# croky_b_1_7_mini.net
KiCad netlist of a schematic drawn in EAGLE
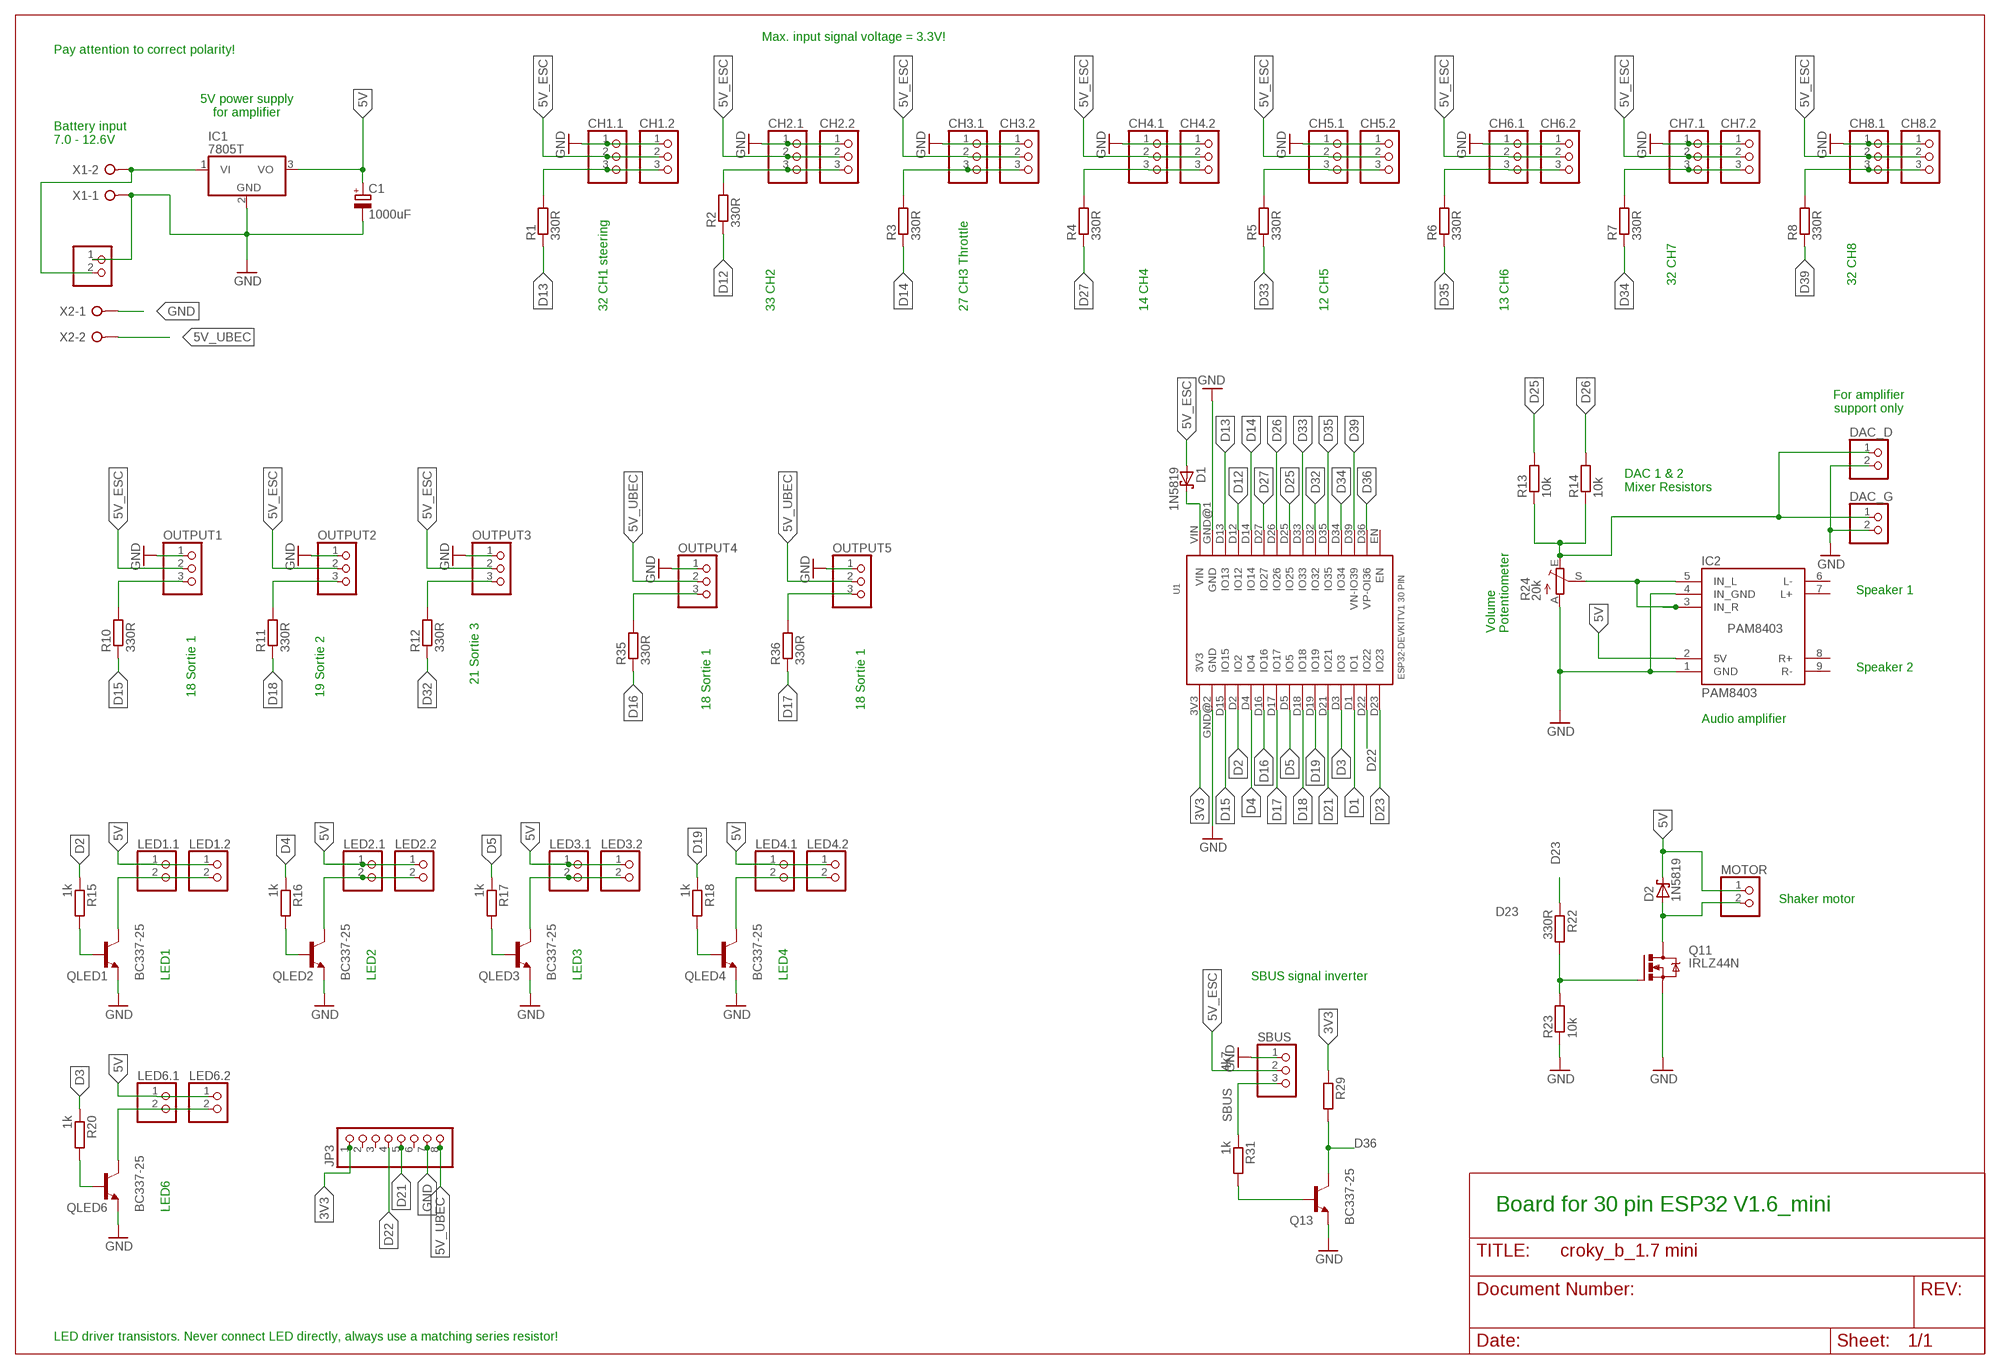
[diagram p0: schematic, sheet 1]

(export (version "E")
  (design (tool "Eeschema 10.0.6"))
  (components
    (comp (ref "C1")
      (value "1000uF")
      (footprint "eagle-import:E5-10,5")
      (libsource (lib "eagle-import") (part "CPOL-EUE5-10.5"))
    )
    (comp (ref "CH1.1")
      (value "PINHD-1X3")
      (footprint "eagle-import:1X03")
      (libsource (lib "eagle-import") (part "PINHD-1X3"))
    )
    (comp (ref "CH1.2")
      (value "PINHD-1X3")
      (footprint "eagle-import:1X03")
      (libsource (lib "eagle-import") (part "PINHD-1X3"))
    )
    (comp (ref "CH2.1")
      (value "PINHD-1X3")
      (footprint "eagle-import:1X03")
      (libsource (lib "eagle-import") (part "PINHD-1X3"))
    )
    (comp (ref "CH2.2")
      (value "PINHD-1X3")
      (footprint "eagle-import:1X03")
      (libsource (lib "eagle-import") (part "PINHD-1X3"))
    )
    (comp (ref "CH3.1")
      (value "PINHD-1X3")
      (footprint "eagle-import:1X03")
      (libsource (lib "eagle-import") (part "PINHD-1X3"))
    )
    (comp (ref "CH3.2")
      (value "PINHD-1X3")
      (footprint "eagle-import:1X03")
      (libsource (lib "eagle-import") (part "PINHD-1X3"))
    )
    (comp (ref "CH4.1")
      (value "PINHD-1X3")
      (footprint "eagle-import:1X03")
      (libsource (lib "eagle-import") (part "PINHD-1X3"))
    )
    (comp (ref "CH4.2")
      (value "PINHD-1X3")
      (footprint "eagle-import:1X03")
      (libsource (lib "eagle-import") (part "PINHD-1X3"))
    )
    (comp (ref "CH5.1")
      (value "PINHD-1X3")
      (footprint "eagle-import:1X03")
      (libsource (lib "eagle-import") (part "PINHD-1X3"))
    )
    (comp (ref "CH5.2")
      (value "PINHD-1X3")
      (footprint "eagle-import:1X03")
      (libsource (lib "eagle-import") (part "PINHD-1X3"))
    )
    (comp (ref "CH6.1")
      (value "PINHD-1X3")
      (footprint "eagle-import:1X03")
      (libsource (lib "eagle-import") (part "PINHD-1X3"))
    )
    (comp (ref "CH6.2")
      (value "PINHD-1X3")
      (footprint "eagle-import:1X03")
      (libsource (lib "eagle-import") (part "PINHD-1X3"))
    )
    (comp (ref "CH7.1")
      (value "PINHD-1X3")
      (footprint "eagle-import:1X03")
      (libsource (lib "eagle-import") (part "PINHD-1X3"))
    )
    (comp (ref "CH7.2")
      (value "PINHD-1X3")
      (footprint "eagle-import:1X03")
      (libsource (lib "eagle-import") (part "PINHD-1X3"))
    )
    (comp (ref "CH8.1")
      (value "PINHD-1X3")
      (footprint "eagle-import:1X03")
      (libsource (lib "eagle-import") (part "PINHD-1X3"))
    )
    (comp (ref "CH8.2")
      (value "PINHD-1X3")
      (footprint "eagle-import:1X03")
      (libsource (lib "eagle-import") (part "PINHD-1X3"))
    )
    (comp (ref "D1")
      (value "1N5819")
      (footprint "eagle-import:DO35-7")
      (libsource (lib "eagle-import") (part "SCHOTTKY-DIODEDO35-7"))
    )
    (comp (ref "D2")
      (value "1N5819")
      (footprint "eagle-import:DO35-7")
      (libsource (lib "eagle-import") (part "SCHOTTKY-DIODEDO35-7"))
    )
    (comp (ref "DAC_D")
      (value "PINHD-1X2")
      (footprint "eagle-import:1X02")
      (libsource (lib "eagle-import") (part "PINHD-1X2"))
    )
    (comp (ref "DAC_G")
      (value "PINHD-1X2")
      (footprint "eagle-import:1X02")
      (libsource (lib "eagle-import") (part "PINHD-1X2"))
    )
    (comp (ref "IC1")
      (value "7805T")
      (footprint "eagle-import:TO220H")
      (libsource (lib "eagle-import") (part "78T05"))
    )
    (comp (ref "IC2")
      (value "PAM8403")
      (footprint "eagle-import:PAM8403")
      (libsource (lib "eagle-import") (part "PAM8403"))
    )
    (comp (ref "JP3")
      (value "PINHD-1X8")
      (footprint "eagle-import:1X08")
      (libsource (lib "eagle-import") (part "PINHD-1X8"))
    )
    (comp (ref "LED1.1")
      (value "PINHD-1X2")
      (footprint "eagle-import:1X02")
      (libsource (lib "eagle-import") (part "PINHD-1X2"))
    )
    (comp (ref "LED1.2")
      (value "PINHD-1X2")
      (footprint "eagle-import:1X02")
      (libsource (lib "eagle-import") (part "PINHD-1X2"))
    )
    (comp (ref "LED2.1")
      (value "PINHD-1X2")
      (footprint "eagle-import:1X02")
      (libsource (lib "eagle-import") (part "PINHD-1X2"))
    )
    (comp (ref "LED2.2")
      (value "PINHD-1X2")
      (footprint "eagle-import:1X02")
      (libsource (lib "eagle-import") (part "PINHD-1X2"))
    )
    (comp (ref "LED3.1")
      (value "PINHD-1X2")
      (footprint "eagle-import:1X02")
      (libsource (lib "eagle-import") (part "PINHD-1X2"))
    )
    (comp (ref "LED3.2")
      (value "PINHD-1X2")
      (footprint "eagle-import:1X02")
      (libsource (lib "eagle-import") (part "PINHD-1X2"))
    )
    (comp (ref "LED4.1")
      (value "PINHD-1X2")
      (footprint "eagle-import:1X02")
      (libsource (lib "eagle-import") (part "PINHD-1X2"))
    )
    (comp (ref "LED4.2")
      (value "PINHD-1X2")
      (footprint "eagle-import:1X02")
      (libsource (lib "eagle-import") (part "PINHD-1X2"))
    )
    (comp (ref "LED6.1")
      (value "PINHD-1X2")
      (footprint "eagle-import:1X02")
      (libsource (lib "eagle-import") (part "PINHD-1X2"))
    )
    (comp (ref "LED6.2")
      (value "PINHD-1X2")
      (footprint "eagle-import:1X02")
      (libsource (lib "eagle-import") (part "PINHD-1X2"))
    )
    (comp (ref "MOTOR")
      (value "PINHD-1X2")
      (footprint "eagle-import:1X02")
      (libsource (lib "eagle-import") (part "PINHD-1X2"))
    )
    (comp (ref "MOTOR2")
      (value "PINHD-1X2")
      (footprint "eagle-import:1X02")
      (libsource (lib "eagle-import") (part "PINHD-1X2"))
    )
    (comp (ref "OUTPUT1")
      (value "PINHD-1X3")
      (footprint "eagle-import:1X03")
      (libsource (lib "eagle-import") (part "PINHD-1X3"))
    )
    (comp (ref "OUTPUT2")
      (value "PINHD-1X3")
      (footprint "eagle-import:1X03")
      (libsource (lib "eagle-import") (part "PINHD-1X3"))
    )
    (comp (ref "OUTPUT3")
      (value "PINHD-1X3")
      (footprint "eagle-import:1X03")
      (libsource (lib "eagle-import") (part "PINHD-1X3"))
    )
    (comp (ref "OUTPUT4")
      (value "PINHD-1X3")
      (footprint "eagle-import:1X03")
      (libsource (lib "eagle-import") (part "PINHD-1X3"))
    )
    (comp (ref "OUTPUT5")
      (value "PINHD-1X3")
      (footprint "eagle-import:1X03")
      (libsource (lib "eagle-import") (part "PINHD-1X3"))
    )
    (comp (ref "Q11")
      (value "IRLZ44N")
      (footprint "eagle-import:TO220BV")
      (libsource (lib "eagle-import") (part "IRF540"))
    )
    (comp (ref "Q13")
      (value "BC337-25")
      (footprint "eagle-import:TO92")
      (libsource (lib "eagle-import") (part "BC337-25"))
    )
    (comp (ref "QLED1")
      (value "BC337-25")
      (footprint "eagle-import:TO92")
      (libsource (lib "eagle-import") (part "BC337-25"))
    )
    (comp (ref "QLED2")
      (value "BC337-25")
      (footprint "eagle-import:TO92")
      (libsource (lib "eagle-import") (part "BC337-25"))
    )
    (comp (ref "QLED3")
      (value "BC337-25")
      (footprint "eagle-import:TO92")
      (libsource (lib "eagle-import") (part "BC337-25"))
    )
    (comp (ref "QLED4")
      (value "BC337-25")
      (footprint "eagle-import:TO92")
      (libsource (lib "eagle-import") (part "BC337-25"))
    )
    (comp (ref "QLED6")
      (value "BC337-25")
      (footprint "eagle-import:TO92")
      (libsource (lib "eagle-import") (part "BC337-25"))
    )
    (comp (ref "R1")
      (value "330R")
      (footprint "eagle-import:0207_2V")
      (libsource (lib "eagle-import") (part "R-EU_0207/2V"))
    )
    (comp (ref "R2")
      (value "330R")
      (footprint "eagle-import:0207_2V")
      (libsource (lib "eagle-import") (part "R-EU_0207/2V"))
    )
    (comp (ref "R3")
      (value "330R")
      (footprint "eagle-import:0207_2V")
      (fields (field (name "SPICEPREFIX") "R"))
      (libsource (lib "eagle-import") (part "R-EU_0207/2V"))
    )
    (comp (ref "R4")
      (value "330R")
      (footprint "eagle-import:0207_2V")
      (libsource (lib "eagle-import") (part "R-EU_0207/2V"))
    )
    (comp (ref "R5")
      (value "330R")
      (footprint "eagle-import:0207_2V")
      (libsource (lib "eagle-import") (part "R-EU_0207/2V"))
    )
    (comp (ref "R6")
      (value "330R")
      (footprint "eagle-import:0207_2V")
      (libsource (lib "eagle-import") (part "R-EU_0207/2V"))
    )
    (comp (ref "R7")
      (value "330R")
      (footprint "eagle-import:0207_2V")
      (libsource (lib "eagle-import") (part "R-EU_0207/2V"))
    )
    (comp (ref "R8")
      (value "330R")
      (footprint "eagle-import:0207_2V")
      (libsource (lib "eagle-import") (part "R-EU_0207/2V"))
    )
    (comp (ref "R10")
      (value "330R")
      (footprint "eagle-import:0207_2V")
      (libsource (lib "eagle-import") (part "R-EU_0207/2V"))
    )
    (comp (ref "R11")
      (value "330R")
      (footprint "eagle-import:0207_2V")
      (libsource (lib "eagle-import") (part "R-EU_0207/2V"))
    )
    (comp (ref "R12")
      (value "330R")
      (footprint "eagle-import:0207_2V")
      (libsource (lib "eagle-import") (part "R-EU_0207/2V"))
    )
    (comp (ref "R13")
      (value "10k")
      (footprint "eagle-import:0207_10")
      (libsource (lib "eagle-import") (part "R-EU_0207/10"))
    )
    (comp (ref "R14")
      (value "10k")
      (footprint "eagle-import:0207_10")
      (libsource (lib "eagle-import") (part "R-EU_0207/10"))
    )
    (comp (ref "R15")
      (value "1k")
      (footprint "eagle-import:0207_2V")
      (libsource (lib "eagle-import") (part "R-EU_0207/2V"))
    )
    (comp (ref "R16")
      (value "1k")
      (footprint "eagle-import:0207_2V")
      (libsource (lib "eagle-import") (part "R-EU_0207/2V"))
    )
    (comp (ref "R17")
      (value "1k")
      (footprint "eagle-import:0207_2V")
      (libsource (lib "eagle-import") (part "R-EU_0207/2V"))
    )
    (comp (ref "R18")
      (value "1k")
      (footprint "eagle-import:0207_2V")
      (libsource (lib "eagle-import") (part "R-EU_0207/2V"))
    )
    (comp (ref "R20")
      (value "1k")
      (footprint "eagle-import:0207_2V")
      (libsource (lib "eagle-import") (part "R-EU_0207/2V"))
    )
    (comp (ref "R22")
      (value "330R")
      (footprint "eagle-import:0207_2V")
      (libsource (lib "eagle-import") (part "R-EU_0207/2V"))
    )
    (comp (ref "R23")
      (value "10k")
      (footprint "eagle-import:0207_2V")
      (libsource (lib "eagle-import") (part "R-EU_0207/2V"))
    )
    (comp (ref "R24")
      (value "20k")
      (footprint "eagle-import:S64W")
      (libsource (lib "eagle-import") (part "TRIM_EU-S64W"))
    )
    (comp (ref "R29")
      (value "4k7")
      (footprint "eagle-import:0207_2V")
      (libsource (lib "eagle-import") (part "R-EU_0207/2V"))
    )
    (comp (ref "R31")
      (value "1k")
      (footprint "eagle-import:0207_2V")
      (libsource (lib "eagle-import") (part "R-EU_0207/2V"))
    )
    (comp (ref "R35")
      (value "330R")
      (footprint "eagle-import:0207_2V")
      (libsource (lib "eagle-import") (part "R-EU_0207/2V"))
    )
    (comp (ref "R36")
      (value "330R")
      (footprint "eagle-import:0207_2V")
      (libsource (lib "eagle-import") (part "R-EU_0207/2V"))
    )
    (comp (ref "SBUS")
      (value "PINHD-1X3")
      (footprint "eagle-import:1X03")
      (libsource (lib "eagle-import") (part "PINHD-1X3"))
    )
    (comp (ref "U1")
      (value "ESP32DEVKITV1")
      (footprint "eagle-import:ESP32-DEVKITV1")
      (libsource (lib "eagle-import") (part "ESP32DEVKITV1"))
    )
    (comp (ref "X1")
      (value "W237-02P")
      (footprint "eagle-import:W237-132")
      (libsource (lib "eagle-import") (part "W237-02P"))
    )
    (comp (ref "X2")
      (value "W237-02P")
      (footprint "eagle-import:W237-132")
      (libsource (lib "eagle-import") (part "W237-02P"))
    )
  )
  (nets
    (net (code "1") (name "/SBUS") (class "Default")
      (node (ref "R31") (pin "1") (pinfunction "1_1") (pintype "passive"))
      (node (ref "SBUS") (pin "3") (pinfunction "3_3") (pintype "passive"))
    )
    (net (code "2") (name "3V3") (class "Default")
      (node (ref "JP3") (pin "1") (pinfunction "1_1") (pintype "passive"))
      (node (ref "R29") (pin "1") (pinfunction "1_1") (pintype "passive"))
      (node (ref "U1") (pin "3V3") (pinfunction "3V3_3V3") (pintype "bidirectional"))
    )
    (net (code "3") (name "5V") (class "Default")
      (node (ref "C1") (pin "+") (pinfunction "+_+") (pintype "passive"))
      (node (ref "D2") (pin "C") (pinfunction "C_C") (pintype "passive"))
      (node (ref "IC1") (pin "3") (pinfunction "VO_3") (pintype "passive"))
      (node (ref "IC2") (pin "2") (pinfunction "5V_2") (pintype "input"))
      (node (ref "LED1.1") (pin "1") (pinfunction "1_1") (pintype "passive"))
      (node (ref "LED1.2") (pin "1") (pinfunction "1_1") (pintype "passive"))
      (node (ref "LED2.1") (pin "1") (pinfunction "1_1") (pintype "passive"))
      (node (ref "LED2.2") (pin "1") (pinfunction "1_1") (pintype "passive"))
      (node (ref "LED3.1") (pin "1") (pinfunction "1_1") (pintype "passive"))
      (node (ref "LED3.2") (pin "1") (pinfunction "1_1") (pintype "passive"))
      (node (ref "LED4.1") (pin "1") (pinfunction "1_1") (pintype "passive"))
      (node (ref "LED4.2") (pin "1") (pinfunction "1_1") (pintype "passive"))
      (node (ref "LED6.1") (pin "1") (pinfunction "1_1") (pintype "passive"))
      (node (ref "LED6.2") (pin "1") (pinfunction "1_1") (pintype "passive"))
      (node (ref "MOTOR") (pin "1") (pinfunction "1_1") (pintype "passive"))
    )
    (net (code "4") (name "5V_ESC") (class "Default")
      (node (ref "CH1.1") (pin "2") (pinfunction "2_2") (pintype "passive"))
      (node (ref "CH1.2") (pin "2") (pinfunction "2_2") (pintype "passive"))
      (node (ref "CH2.1") (pin "2") (pinfunction "2_2") (pintype "passive"))
      (node (ref "CH2.2") (pin "2") (pinfunction "2_2") (pintype "passive"))
      (node (ref "CH3.1") (pin "2") (pinfunction "2_2") (pintype "passive"))
      (node (ref "CH3.2") (pin "2") (pinfunction "2_2") (pintype "passive"))
      (node (ref "CH4.1") (pin "2") (pinfunction "2_2") (pintype "passive"))
      (node (ref "CH4.2") (pin "2") (pinfunction "2_2") (pintype "passive"))
      (node (ref "CH5.1") (pin "2") (pinfunction "2_2") (pintype "passive"))
      (node (ref "CH5.2") (pin "2") (pinfunction "2_2") (pintype "passive"))
      (node (ref "CH6.1") (pin "2") (pinfunction "2_2") (pintype "passive"))
      (node (ref "CH6.2") (pin "2") (pinfunction "2_2") (pintype "passive"))
      (node (ref "CH7.1") (pin "2") (pinfunction "2_2") (pintype "passive"))
      (node (ref "CH7.2") (pin "2") (pinfunction "2_2") (pintype "passive"))
      (node (ref "CH8.1") (pin "2") (pinfunction "2_2") (pintype "passive"))
      (node (ref "CH8.2") (pin "2") (pinfunction "2_2") (pintype "passive"))
      (node (ref "D1") (pin "A") (pinfunction "A_A") (pintype "passive"))
      (node (ref "OUTPUT1") (pin "2") (pinfunction "2_2") (pintype "passive"))
      (node (ref "OUTPUT2") (pin "2") (pinfunction "2_2") (pintype "passive"))
      (node (ref "OUTPUT3") (pin "2") (pinfunction "2_2") (pintype "passive"))
      (node (ref "SBUS") (pin "2") (pinfunction "2_2") (pintype "passive"))
    )
    (net (code "5") (name "5V_UBEC") (class "Default")
      (node (ref "JP3") (pin "8") (pinfunction "8_8") (pintype "passive"))
      (node (ref "OUTPUT4") (pin "2") (pinfunction "2_2") (pintype "passive"))
      (node (ref "OUTPUT5") (pin "2") (pinfunction "2_2") (pintype "passive"))
      (node (ref "X2") (pin "2") (pinfunction "KL_2") (pintype "passive"))
    )
    (net (code "6") (name "D1") (class "Default")
      (node (ref "U1") (pin "D1") (pinfunction "IO1_D1") (pintype "bidirectional"))
    )
    (net (code "7") (name "D2") (class "Default")
      (node (ref "R15") (pin "1") (pinfunction "1_1") (pintype "passive"))
      (node (ref "U1") (pin "D2") (pinfunction "IO2_D2") (pintype "bidirectional"))
    )
    (net (code "8") (name "D3") (class "Default")
      (node (ref "R20") (pin "1") (pinfunction "1_1") (pintype "passive"))
      (node (ref "U1") (pin "D3") (pinfunction "IO3_D3") (pintype "bidirectional"))
    )
    (net (code "9") (name "D4") (class "Default")
      (node (ref "R16") (pin "1") (pinfunction "1_1") (pintype "passive"))
      (node (ref "U1") (pin "D4") (pinfunction "IO4_D4") (pintype "bidirectional"))
    )
    (net (code "10") (name "D5") (class "Default")
      (node (ref "R17") (pin "1") (pinfunction "1_1") (pintype "passive"))
      (node (ref "U1") (pin "D5") (pinfunction "IO5_D5") (pintype "bidirectional"))
    )
    (net (code "11") (name "D12") (class "Default")
      (node (ref "R2") (pin "1") (pinfunction "1_1") (pintype "passive"))
      (node (ref "U1") (pin "D12") (pinfunction "IO12_D12") (pintype "bidirectional"))
    )
    (net (code "12") (name "D13") (class "Default")
      (node (ref "R1") (pin "1") (pinfunction "1_1") (pintype "passive"))
      (node (ref "U1") (pin "D13") (pinfunction "IO13_D13") (pintype "bidirectional"))
    )
    (net (code "13") (name "D14") (class "Default")
      (node (ref "R3") (pin "1") (pinfunction "1_1") (pintype "passive"))
      (node (ref "U1") (pin "D14") (pinfunction "IO14_D14") (pintype "bidirectional"))
    )
    (net (code "14") (name "D15") (class "Default")
      (node (ref "R10") (pin "1") (pinfunction "1_1") (pintype "passive"))
      (node (ref "U1") (pin "D15") (pinfunction "IO15_D15") (pintype "bidirectional"))
    )
    (net (code "15") (name "D16") (class "Default")
      (node (ref "R35") (pin "1") (pinfunction "1_1") (pintype "passive"))
      (node (ref "U1") (pin "D16") (pinfunction "IO16_D16") (pintype "bidirectional"))
    )
    (net (code "16") (name "D17") (class "Default")
      (node (ref "R36") (pin "1") (pinfunction "1_1") (pintype "passive"))
      (node (ref "U1") (pin "D17") (pinfunction "IO17_D17") (pintype "bidirectional"))
    )
    (net (code "17") (name "D18") (class "Default")
      (node (ref "R11") (pin "1") (pinfunction "1_1") (pintype "passive"))
      (node (ref "U1") (pin "D18") (pinfunction "IO18_D18") (pintype "bidirectional"))
    )
    (net (code "18") (name "D19") (class "Default")
      (node (ref "R18") (pin "1") (pinfunction "1_1") (pintype "passive"))
      (node (ref "U1") (pin "D19") (pinfunction "IO19_D19") (pintype "bidirectional"))
    )
    (net (code "19") (name "D21") (class "Default")
      (node (ref "JP3") (pin "5") (pinfunction "5_5") (pintype "passive"))
      (node (ref "U1") (pin "D21") (pinfunction "IO21_D21") (pintype "bidirectional"))
    )
    (net (code "20") (name "D22") (class "Default")
      (node (ref "JP3") (pin "4") (pinfunction "4_4") (pintype "passive"))
      (node (ref "U1") (pin "D22") (pinfunction "IO22_D22") (pintype "bidirectional"))
    )
    (net (code "21") (name "D23") (class "Default")
      (node (ref "R22") (pin "1") (pinfunction "1_1") (pintype "passive"))
      (node (ref "U1") (pin "D23") (pinfunction "IO23_D23") (pintype "bidirectional"))
    )
    (net (code "22") (name "D25") (class "Default")
      (node (ref "R13") (pin "2") (pinfunction "2_2") (pintype "passive"))
      (node (ref "U1") (pin "D25") (pinfunction "IO25_D25") (pintype "bidirectional"))
    )
    (net (code "23") (name "D26") (class "Default")
      (node (ref "R14") (pin "2") (pinfunction "2_2") (pintype "passive"))
      (node (ref "U1") (pin "D26") (pinfunction "IO26_D26") (pintype "bidirectional"))
    )
    (net (code "24") (name "D27") (class "Default")
      (node (ref "R4") (pin "1") (pinfunction "1_1") (pintype "passive"))
      (node (ref "U1") (pin "D27") (pinfunction "IO27_D27") (pintype "bidirectional"))
    )
    (net (code "25") (name "D32") (class "Default")
      (node (ref "R12") (pin "1") (pinfunction "1_1") (pintype "passive"))
      (node (ref "U1") (pin "D32") (pinfunction "IO32_D32") (pintype "bidirectional"))
    )
    (net (code "26") (name "D33") (class "Default")
      (node (ref "R5") (pin "1") (pinfunction "1_1") (pintype "passive"))
      (node (ref "U1") (pin "D33") (pinfunction "IO33_D33") (pintype "bidirectional"))
    )
    (net (code "27") (name "D34") (class "Default")
      (node (ref "R7") (pin "1") (pinfunction "1_1") (pintype "passive"))
      (node (ref "U1") (pin "D34") (pinfunction "IO34_D34") (pintype "bidirectional"))
    )
    (net (code "28") (name "D35") (class "Default")
      (node (ref "R6") (pin "1") (pinfunction "1_1") (pintype "passive"))
      (node (ref "U1") (pin "D35") (pinfunction "IO35_D35") (pintype "bidirectional"))
    )
    (net (code "29") (name "D36") (class "Default")
      (node (ref "Q13") (pin "3") (pinfunction "C_3") (pintype "passive"))
      (node (ref "R29") (pin "2") (pinfunction "2_2") (pintype "passive"))
      (node (ref "U1") (pin "D36") (pinfunction "VP-OI36_D36") (pintype "bidirectional"))
    )
    (net (code "30") (name "D39") (class "Default")
      (node (ref "R8") (pin "1") (pinfunction "1_1") (pintype "passive"))
      (node (ref "U1") (pin "D39") (pinfunction "VN-IO39_D39") (pintype "bidirectional"))
    )
    (net (code "31") (name "GND") (class "Default")
      (node (ref "C1") (pin "-") (pinfunction "-_-") (pintype "passive"))
      (node (ref "CH1.1") (pin "1") (pinfunction "1_1") (pintype "passive"))
      (node (ref "CH1.2") (pin "1") (pinfunction "1_1") (pintype "passive"))
      (node (ref "CH2.1") (pin "1") (pinfunction "1_1") (pintype "passive"))
      (node (ref "CH2.2") (pin "1") (pinfunction "1_1") (pintype "passive"))
      (node (ref "CH3.1") (pin "1") (pinfunction "1_1") (pintype "passive"))
      (node (ref "CH3.2") (pin "1") (pinfunction "1_1") (pintype "passive"))
      (node (ref "CH4.1") (pin "1") (pinfunction "1_1") (pintype "passive"))
      (node (ref "CH4.2") (pin "1") (pinfunction "1_1") (pintype "passive"))
      (node (ref "CH5.1") (pin "1") (pinfunction "1_1") (pintype "passive"))
      (node (ref "CH5.2") (pin "1") (pinfunction "1_1") (pintype "passive"))
      (node (ref "CH6.1") (pin "1") (pinfunction "1_1") (pintype "passive"))
      (node (ref "CH6.2") (pin "1") (pinfunction "1_1") (pintype "passive"))
      (node (ref "CH7.1") (pin "1") (pinfunction "1_1") (pintype "passive"))
      (node (ref "CH7.2") (pin "1") (pinfunction "1_1") (pintype "passive"))
      (node (ref "CH8.1") (pin "1") (pinfunction "1_1") (pintype "passive"))
      (node (ref "CH8.2") (pin "1") (pinfunction "1_1") (pintype "passive"))
      (node (ref "DAC_D") (pin "2") (pinfunction "2_2") (pintype "passive"))
      (node (ref "DAC_G") (pin "2") (pinfunction "2_2") (pintype "passive"))
      (node (ref "IC1") (pin "2") (pinfunction "GND_2") (pintype "passive"))
      (node (ref "IC2") (pin "1") (pinfunction "GND_1") (pintype "input"))
      (node (ref "IC2") (pin "4") (pinfunction "IN_GND_4") (pintype "input"))
      (node (ref "JP3") (pin "7") (pinfunction "7_7") (pintype "passive"))
      (node (ref "MOTOR2") (pin "1") (pinfunction "1_1") (pintype "passive"))
      (node (ref "OUTPUT1") (pin "1") (pinfunction "1_1") (pintype "passive"))
      (node (ref "OUTPUT2") (pin "1") (pinfunction "1_1") (pintype "passive"))
      (node (ref "OUTPUT3") (pin "1") (pinfunction "1_1") (pintype "passive"))
      (node (ref "OUTPUT4") (pin "1") (pinfunction "1_1") (pintype "passive"))
      (node (ref "OUTPUT5") (pin "1") (pinfunction "1_1") (pintype "passive"))
      (node (ref "Q11") (pin "S") (pinfunction "S_S") (pintype "passive"))
      (node (ref "Q13") (pin "1") (pinfunction "E_1") (pintype "passive"))
      (node (ref "QLED1") (pin "1") (pinfunction "E_1") (pintype "passive"))
      (node (ref "QLED2") (pin "1") (pinfunction "E_1") (pintype "passive"))
      (node (ref "QLED3") (pin "1") (pinfunction "E_1") (pintype "passive"))
      (node (ref "QLED4") (pin "1") (pinfunction "E_1") (pintype "passive"))
      (node (ref "QLED6") (pin "1") (pinfunction "E_1") (pintype "passive"))
      (node (ref "R23") (pin "1") (pinfunction "1_1") (pintype "passive"))
      (node (ref "R24") (pin "A") (pinfunction "A_A") (pintype "passive"))
      (node (ref "SBUS") (pin "1") (pinfunction "1_1") (pintype "passive"))
      (node (ref "U1") (pin "GND@1") (pinfunction "GND_GND@1") (pintype "bidirectional"))
      (node (ref "U1") (pin "GND@2") (pinfunction "GND_GND@2") (pintype "bidirectional"))
      (node (ref "X1") (pin "1") (pinfunction "KL_1") (pintype "passive"))
      (node (ref "X2") (pin "1") (pinfunction "KL_1") (pintype "passive"))
    )
    (net (code "32") (name "Net-(CH1.1-Pad3)") (class "Default")
      (node (ref "CH1.1") (pin "3") (pinfunction "3_3") (pintype "passive"))
      (node (ref "CH1.2") (pin "3") (pinfunction "3_3") (pintype "passive"))
      (node (ref "R1") (pin "2") (pinfunction "2_2") (pintype "passive"))
    )
    (net (code "33") (name "Net-(CH2.1-Pad3)") (class "Default")
      (node (ref "CH2.1") (pin "3") (pinfunction "3_3") (pintype "passive"))
      (node (ref "CH2.2") (pin "3") (pinfunction "3_3") (pintype "passive"))
      (node (ref "R2") (pin "2") (pinfunction "2_2") (pintype "passive"))
    )
    (net (code "34") (name "Net-(CH3.1-Pad3)") (class "Default")
      (node (ref "CH3.1") (pin "3") (pinfunction "3_3") (pintype "passive"))
      (node (ref "CH3.2") (pin "3") (pinfunction "3_3") (pintype "passive"))
      (node (ref "R3") (pin "2") (pinfunction "2_2") (pintype "passive"))
    )
    (net (code "35") (name "Net-(CH4.1-Pad3)") (class "Default")
      (node (ref "CH4.1") (pin "3") (pinfunction "3_3") (pintype "passive"))
      (node (ref "CH4.2") (pin "3") (pinfunction "3_3") (pintype "passive"))
      (node (ref "R4") (pin "2") (pinfunction "2_2") (pintype "passive"))
    )
    (net (code "36") (name "Net-(CH5.1-Pad3)") (class "Default")
      (node (ref "CH5.1") (pin "3") (pinfunction "3_3") (pintype "passive"))
      (node (ref "CH5.2") (pin "3") (pinfunction "3_3") (pintype "passive"))
      (node (ref "R5") (pin "2") (pinfunction "2_2") (pintype "passive"))
    )
    (net (code "37") (name "Net-(CH6.1-Pad3)") (class "Default")
      (node (ref "CH6.1") (pin "3") (pinfunction "3_3") (pintype "passive"))
      (node (ref "CH6.2") (pin "3") (pinfunction "3_3") (pintype "passive"))
      (node (ref "R6") (pin "2") (pinfunction "2_2") (pintype "passive"))
    )
    (net (code "38") (name "Net-(CH7.1-Pad3)") (class "Default")
      (node (ref "CH7.1") (pin "3") (pinfunction "3_3") (pintype "passive"))
      (node (ref "CH7.2") (pin "3") (pinfunction "3_3") (pintype "passive"))
      (node (ref "R7") (pin "2") (pinfunction "2_2") (pintype "passive"))
    )
    (net (code "39") (name "Net-(CH8.1-Pad3)") (class "Default")
      (node (ref "CH8.1") (pin "3") (pinfunction "3_3") (pintype "passive"))
      (node (ref "CH8.2") (pin "3") (pinfunction "3_3") (pintype "passive"))
      (node (ref "R8") (pin "2") (pinfunction "2_2") (pintype "passive"))
    )
    (net (code "40") (name "Net-(D1-PadC)") (class "Default")
      (node (ref "D1") (pin "C") (pinfunction "C_C") (pintype "passive"))
      (node (ref "U1") (pin "VIN") (pinfunction "VIN_VIN") (pintype "bidirectional"))
    )
    (net (code "41") (name "Net-(D2-PadA)") (class "Default")
      (node (ref "D2") (pin "A") (pinfunction "A_A") (pintype "passive"))
      (node (ref "MOTOR") (pin "2") (pinfunction "2_2") (pintype "passive"))
      (node (ref "Q11") (pin "D") (pinfunction "D_D") (pintype "passive"))
    )
    (net (code "42") (name "Net-(DAC_D-Pad1)") (class "Default")
      (node (ref "DAC_D") (pin "1") (pinfunction "1_1") (pintype "passive"))
      (node (ref "DAC_G") (pin "1") (pinfunction "1_1") (pintype "passive"))
      (node (ref "R13") (pin "1") (pinfunction "1_1") (pintype "passive"))
      (node (ref "R14") (pin "1") (pinfunction "1_1") (pintype "passive"))
      (node (ref "R24") (pin "E") (pinfunction "E_E") (pintype "passive"))
    )
    (net (code "43") (name "Net-(IC1-VI)") (class "Default")
      (node (ref "IC1") (pin "1") (pinfunction "VI_1") (pintype "input"))
      (node (ref "MOTOR2") (pin "2") (pinfunction "2_2") (pintype "passive"))
      (node (ref "X1") (pin "2") (pinfunction "KL_2") (pintype "passive"))
    )
    (net (code "44") (name "Net-(IC2-IN_L)") (class "Default")
      (node (ref "IC2") (pin "3") (pinfunction "IN_R_3") (pintype "input"))
      (node (ref "IC2") (pin "5") (pinfunction "IN_L_5") (pintype "input"))
      (node (ref "R24") (pin "S") (pinfunction "S_S") (pintype "passive"))
    )
    (net (code "45") (name "Net-(OUTPUT1-Pad3)") (class "Default")
      (node (ref "OUTPUT1") (pin "3") (pinfunction "3_3") (pintype "passive"))
      (node (ref "R10") (pin "2") (pinfunction "2_2") (pintype "passive"))
    )
    (net (code "46") (name "Net-(OUTPUT2-Pad3)") (class "Default")
      (node (ref "OUTPUT2") (pin "3") (pinfunction "3_3") (pintype "passive"))
      (node (ref "R11") (pin "2") (pinfunction "2_2") (pintype "passive"))
    )
    (net (code "47") (name "Net-(OUTPUT3-Pad3)") (class "Default")
      (node (ref "OUTPUT3") (pin "3") (pinfunction "3_3") (pintype "passive"))
      (node (ref "R12") (pin "2") (pinfunction "2_2") (pintype "passive"))
    )
    (net (code "48") (name "Net-(OUTPUT4-Pad3)") (class "Default")
      (node (ref "OUTPUT4") (pin "3") (pinfunction "3_3") (pintype "passive"))
      (node (ref "R35") (pin "2") (pinfunction "2_2") (pintype "passive"))
    )
    (net (code "49") (name "Net-(OUTPUT5-Pad3)") (class "Default")
      (node (ref "OUTPUT5") (pin "3") (pinfunction "3_3") (pintype "passive"))
      (node (ref "R36") (pin "2") (pinfunction "2_2") (pintype "passive"))
    )
    (net (code "50") (name "Net-(Q11-PadG)") (class "Default")
      (node (ref "Q11") (pin "G") (pinfunction "G_G") (pintype "passive"))
      (node (ref "R22") (pin "2") (pinfunction "2_2") (pintype "passive"))
      (node (ref "R23") (pin "2") (pinfunction "2_2") (pintype "passive"))
    )
    (net (code "51") (name "Net-(Q13-B)") (class "Default")
      (node (ref "Q13") (pin "2") (pinfunction "B_2") (pintype "passive"))
      (node (ref "R31") (pin "2") (pinfunction "2_2") (pintype "passive"))
    )
    (net (code "52") (name "Net-(QLED1-B)") (class "Default")
      (node (ref "QLED1") (pin "2") (pinfunction "B_2") (pintype "passive"))
      (node (ref "R15") (pin "2") (pinfunction "2_2") (pintype "passive"))
    )
    (net (code "53") (name "Net-(QLED1-C)") (class "Default")
      (node (ref "LED1.1") (pin "2") (pinfunction "2_2") (pintype "passive"))
      (node (ref "LED1.2") (pin "2") (pinfunction "2_2") (pintype "passive"))
      (node (ref "QLED1") (pin "3") (pinfunction "C_3") (pintype "passive"))
    )
    (net (code "54") (name "Net-(QLED2-B)") (class "Default")
      (node (ref "QLED2") (pin "2") (pinfunction "B_2") (pintype "passive"))
      (node (ref "R16") (pin "2") (pinfunction "2_2") (pintype "passive"))
    )
    (net (code "55") (name "Net-(QLED2-C)") (class "Default")
      (node (ref "LED2.1") (pin "2") (pinfunction "2_2") (pintype "passive"))
      (node (ref "LED2.2") (pin "2") (pinfunction "2_2") (pintype "passive"))
      (node (ref "QLED2") (pin "3") (pinfunction "C_3") (pintype "passive"))
    )
    (net (code "56") (name "Net-(QLED3-B)") (class "Default")
      (node (ref "QLED3") (pin "2") (pinfunction "B_2") (pintype "passive"))
      (node (ref "R17") (pin "2") (pinfunction "2_2") (pintype "passive"))
    )
    (net (code "57") (name "Net-(QLED3-C)") (class "Default")
      (node (ref "LED3.1") (pin "2") (pinfunction "2_2") (pintype "passive"))
      (node (ref "LED3.2") (pin "2") (pinfunction "2_2") (pintype "passive"))
      (node (ref "QLED3") (pin "3") (pinfunction "C_3") (pintype "passive"))
    )
    (net (code "58") (name "Net-(QLED4-B)") (class "Default")
      (node (ref "QLED4") (pin "2") (pinfunction "B_2") (pintype "passive"))
      (node (ref "R18") (pin "2") (pinfunction "2_2") (pintype "passive"))
    )
    (net (code "59") (name "Net-(QLED4-C)") (class "Default")
      (node (ref "LED4.1") (pin "2") (pinfunction "2_2") (pintype "passive"))
      (node (ref "LED4.2") (pin "2") (pinfunction "2_2") (pintype "passive"))
      (node (ref "QLED4") (pin "3") (pinfunction "C_3") (pintype "passive"))
    )
    (net (code "60") (name "Net-(QLED6-B)") (class "Default")
      (node (ref "QLED6") (pin "2") (pinfunction "B_2") (pintype "passive"))
      (node (ref "R20") (pin "2") (pinfunction "2_2") (pintype "passive"))
    )
    (net (code "61") (name "Net-(QLED6-C)") (class "Default")
      (node (ref "LED6.1") (pin "2") (pinfunction "2_2") (pintype "passive"))
      (node (ref "LED6.2") (pin "2") (pinfunction "2_2") (pintype "passive"))
      (node (ref "QLED6") (pin "3") (pinfunction "C_3") (pintype "passive"))
    )
    (net (code "62") (name "unconnected-(IC2-L+-Pad7)") (class "Default")
      (node (ref "IC2") (pin "7") (pinfunction "L+_7") (pintype "output"))
    )
    (net (code "63") (name "unconnected-(IC2-L--Pad6)") (class "Default")
      (node (ref "IC2") (pin "6") (pinfunction "L-_6") (pintype "output"))
    )
    (net (code "64") (name "unconnected-(IC2-R+-Pad8)") (class "Default")
      (node (ref "IC2") (pin "8") (pinfunction "R+_8") (pintype "output"))
    )
    (net (code "65") (name "unconnected-(IC2-R--Pad9)") (class "Default")
      (node (ref "IC2") (pin "9") (pinfunction "R-_9") (pintype "output"))
    )
    (net (code "66") (name "unconnected-(JP3-Pad2)") (class "Default")
      (node (ref "JP3") (pin "2") (pinfunction "2_2") (pintype "passive"))
    )
    (net (code "67") (name "unconnected-(JP3-Pad3)") (class "Default")
      (node (ref "JP3") (pin "3") (pinfunction "3_3") (pintype "passive"))
    )
    (net (code "68") (name "unconnected-(JP3-Pad6)") (class "Default")
      (node (ref "JP3") (pin "6") (pinfunction "6_6") (pintype "passive"))
    )
    (net (code "69") (name "unconnected-(U1-PadEN)") (class "Default")
      (node (ref "U1") (pin "EN") (pinfunction "EN_EN") (pintype "bidirectional"))
    )
  )
)
